# Pressure_gauge_V3_0.net
KiCad netlist of a schematic drawn in Altium Designer
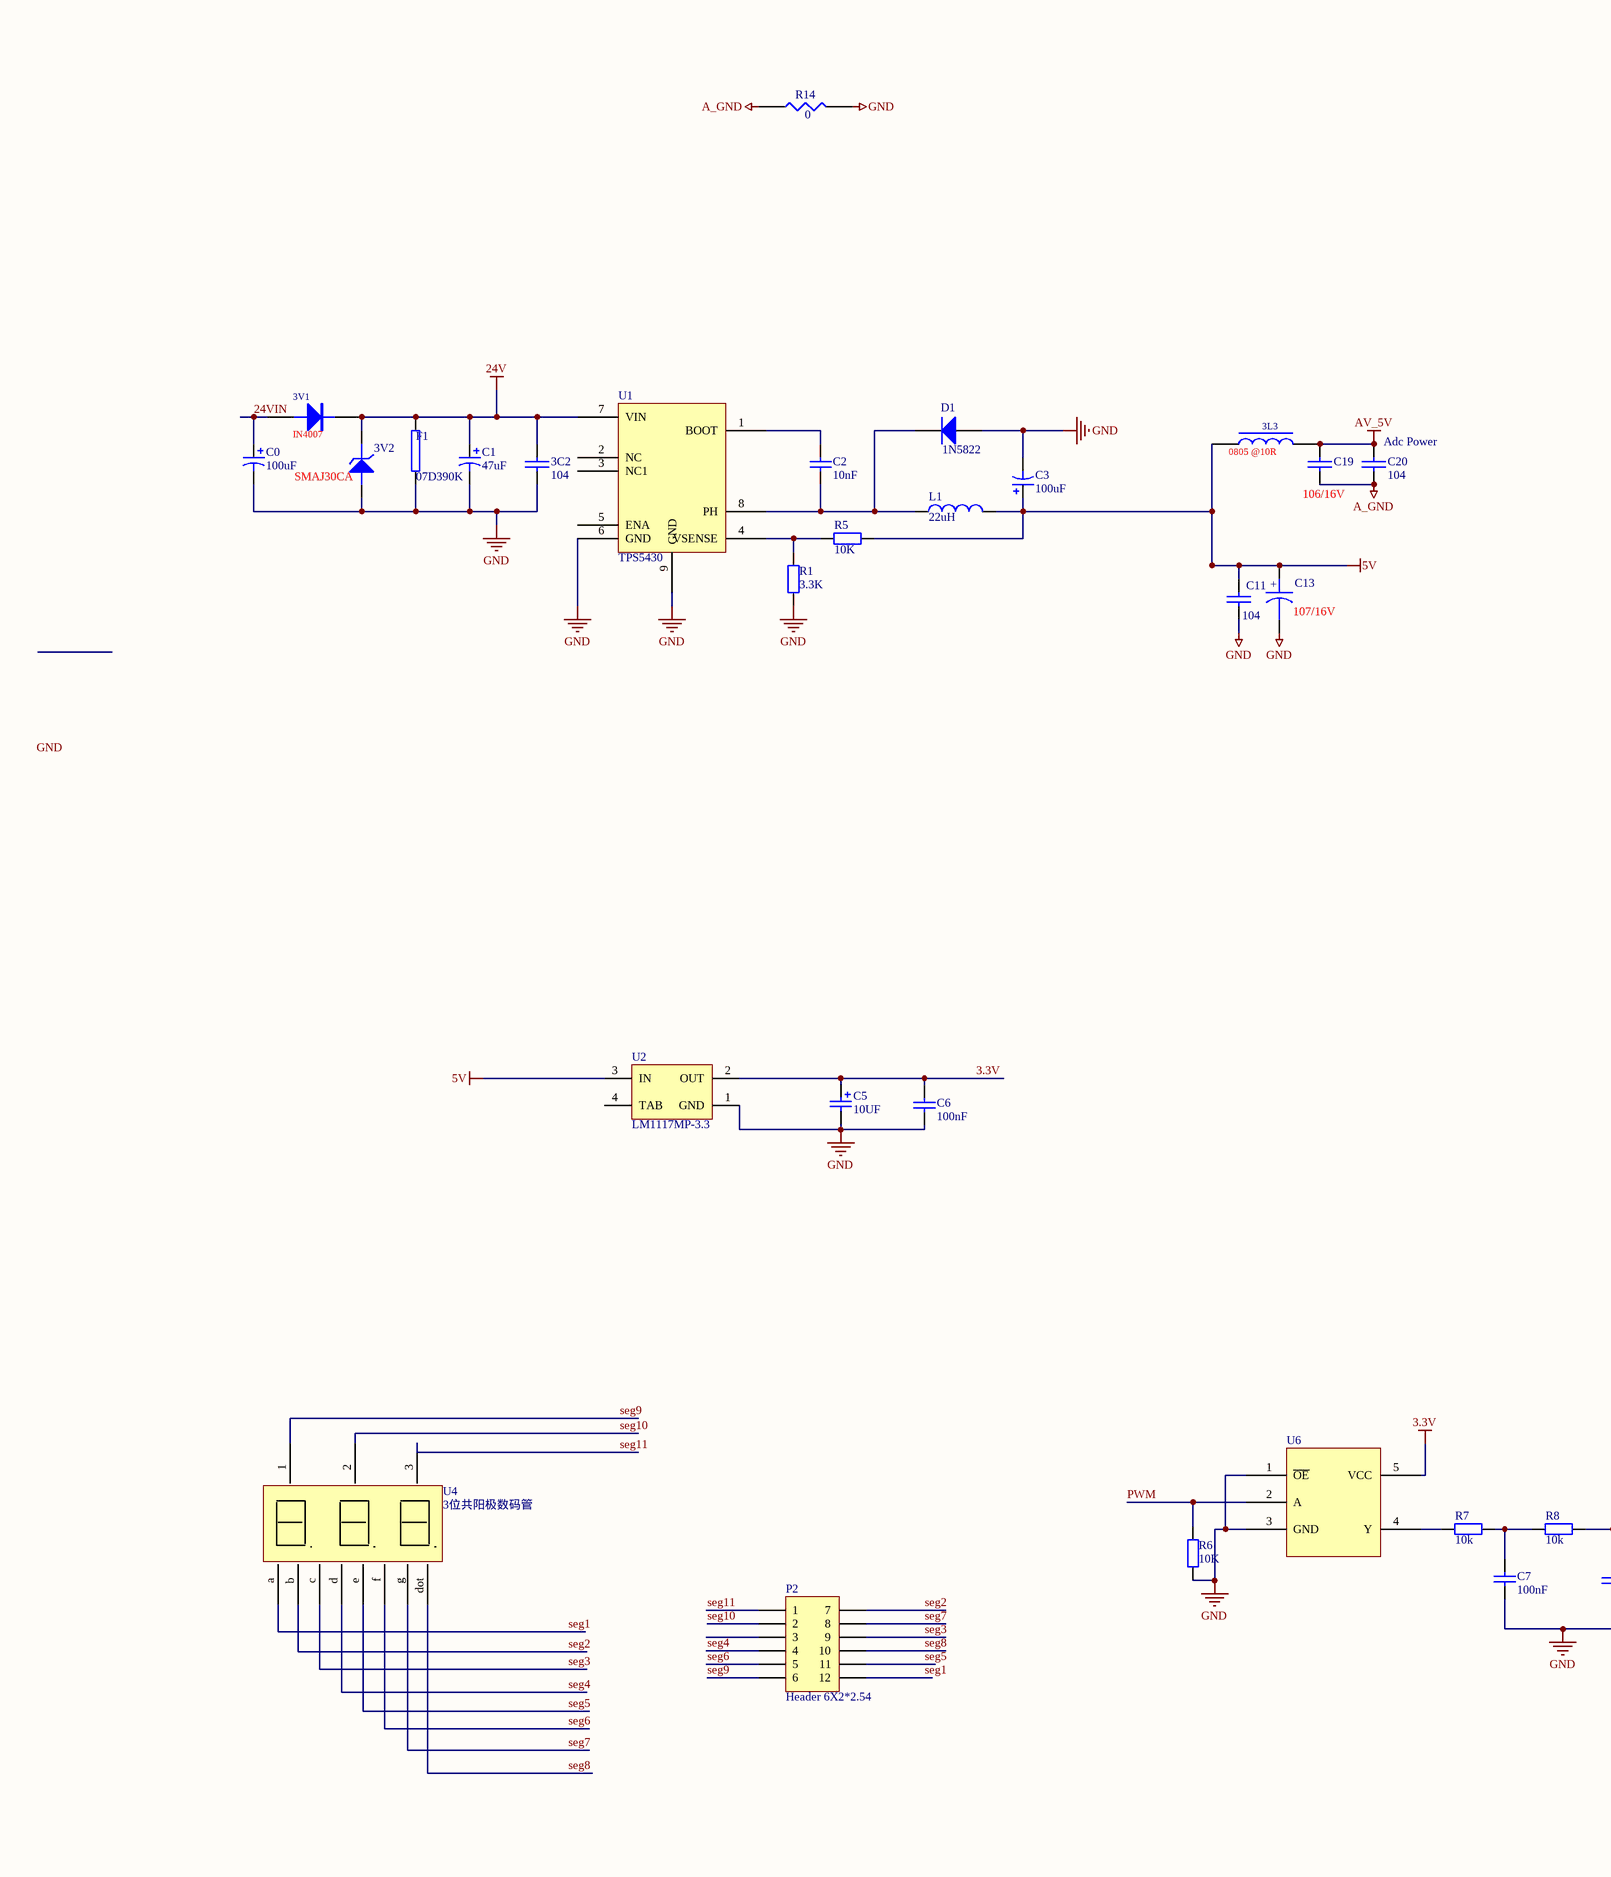
[diagram p0: Pressure_gauge_V3.0.SchDoc, left]
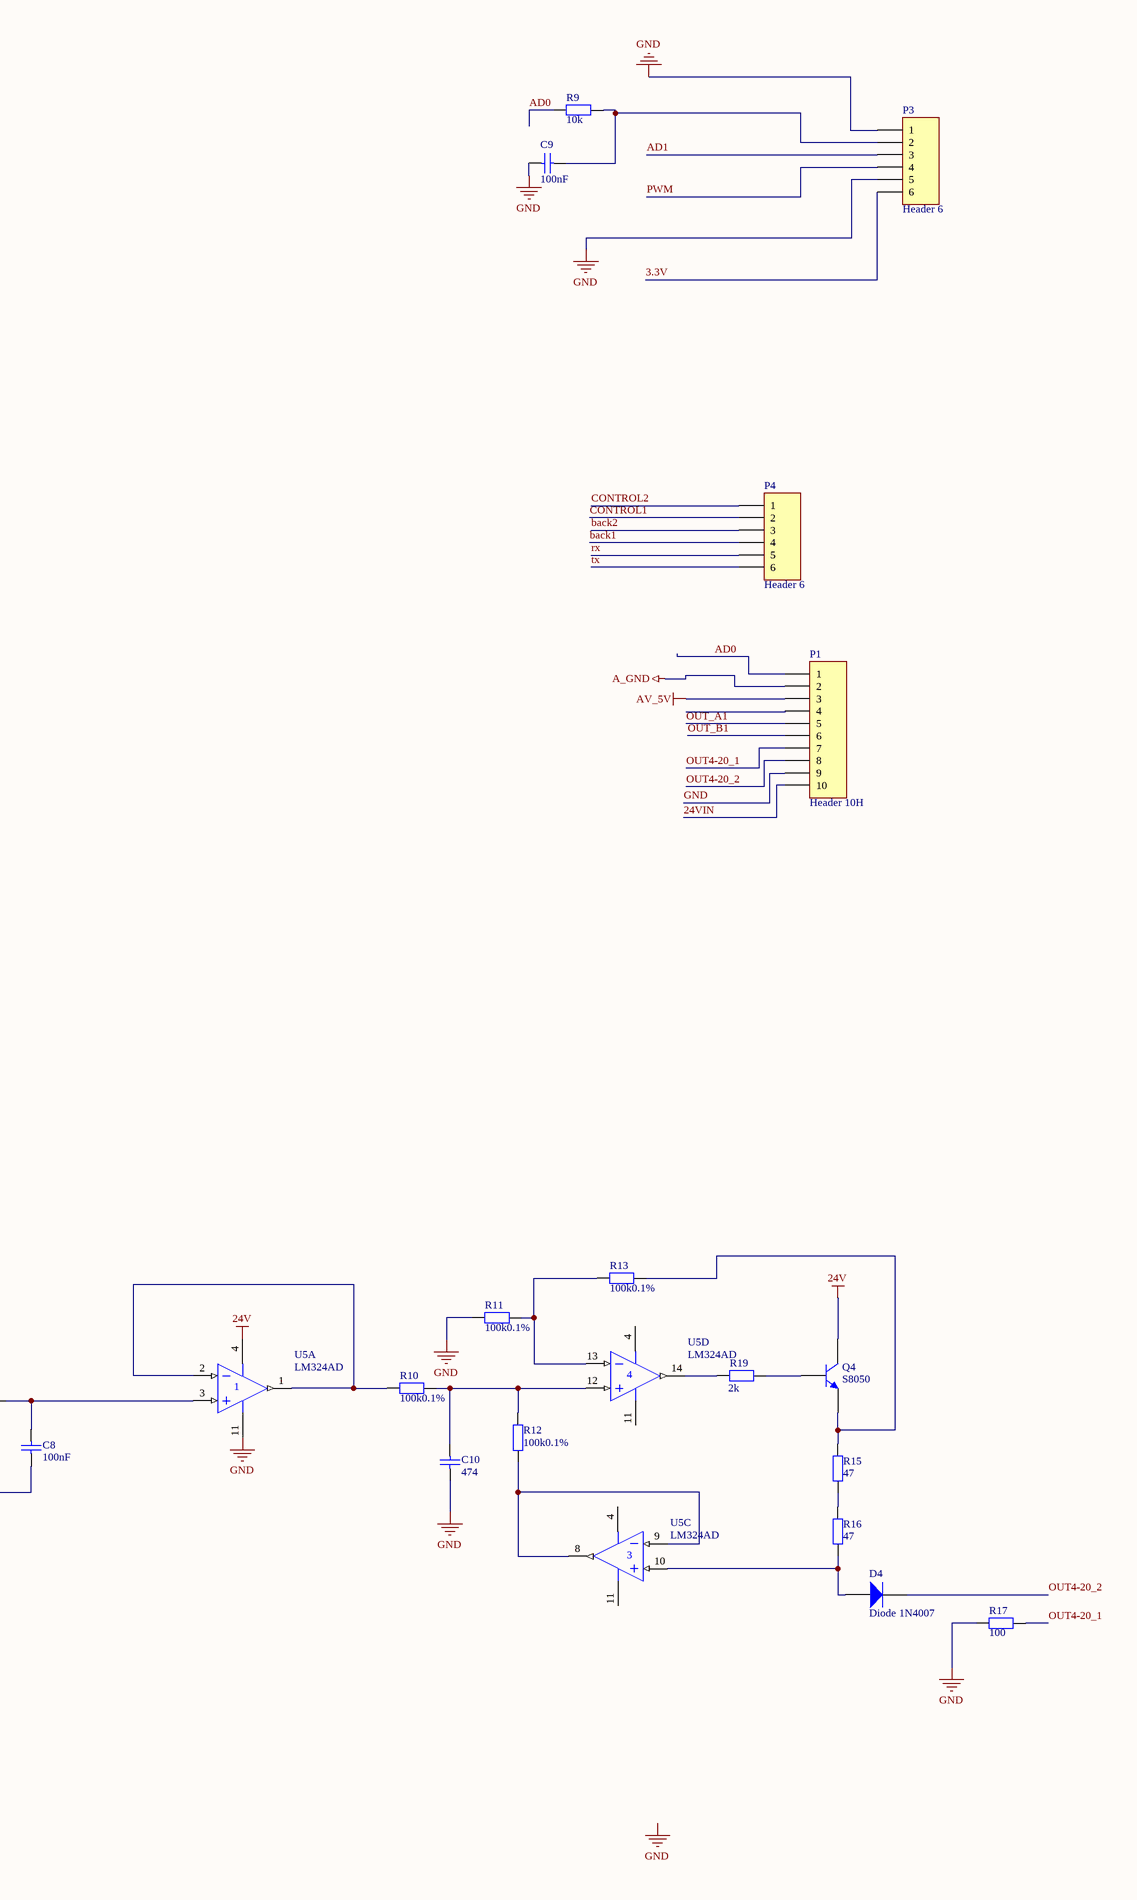
[diagram p1: Pressure_gauge_V3.0.SchDoc, right]

(export (version "E")
  (design (tool "Eeschema 10.0.6"))
  (components
    (comp (ref "3C2")
      (value "104")
      (footprint "0805_C_Y")
      (description "Capacitor")
      (libsource (lib "*") (part "CAP"))
    )
    (comp (ref "3L3")
      (value "0805 @10R")
      (footprint "SMDF4532")
      (description "磁珠")
      (libsource (lib "*") (part "TRANS0"))
    )
    (comp (ref "3V1")
      (value "IN4007")
      (footprint "DO-214AC")
      (description "Diode")
      (libsource (lib "*") (part "DIODE"))
    )
    (comp (ref "3V2")
      (value "SMAJ30CA")
      (footprint "DO-214AA")
      (description "Zener Diode")
      (libsource (lib "*") (part "ZENER3"))
    )
    (comp (ref "C0")
      (value "100uF")
      (footprint "D50")
      (description "Polarized Capacitor (Radial)")
      (fields (field (name "PUBLISHER") "Altium Limited"))
      (libsource (lib "Miscellaneous Devices") (part "Cap Pol1"))
    )
    (comp (ref "C1")
      (value "47uF")
      (footprint "3528 钽电容")
      (description "Polarized Capacitor (Radial)")
      (fields (field (name "PUBLISHER") "Altium Limited"))
      (libsource (lib "Miscellaneous Devices") (part "Cap Pol1"))
    )
    (comp (ref "C2")
      (value "10nF")
      (footprint "0805C")
      (description "Capacitor")
      (fields (field (name "PUBLISHER") "Altium Limited"))
      (libsource (lib "Miscellaneous Devices") (part "Cap"))
    )
    (comp (ref "C3")
      (value "100uF")
      (footprint "1812-PPTC")
      (description "Polarized Capacitor (Radial)")
      (fields (field (name "PUBLISHER") "Altium Limited"))
      (libsource (lib "Miscellaneous Devices") (part "Cap Pol1"))
    )
    (comp (ref "C5")
      (value "10UF")
      (footprint "3216")
      (description "Polarized Capacitor (Axial)")
      (fields (field (name "Comment") "10uf") (field (name "PUBLISHER") "Altium Limited"))
      (libsource (lib "Miscellaneous Devices") (part "Cap Pol2"))
    )
    (comp (ref "C6")
      (value "100nF")
      (footprint "0805_C_Y")
      (description "Capacitor")
      (fields (field (name "Comment") "100nf") (field (name "PUBLISHER") "Altium Limited"))
      (libsource (lib "Miscellaneous Devices") (part "Cap"))
    )
    (comp (ref "C7")
      (value "100nF")
      (footprint "0805_C_Y")
      (description "Capacitor")
      (fields (field (name "Comment") "100nf") (field (name "PUBLISHER") "Altium Limited"))
      (libsource (lib "Miscellaneous Devices") (part "Cap"))
    )
    (comp (ref "C8")
      (value "100nF")
      (footprint "0805_C_Y")
      (description "Capacitor")
      (fields (field (name "Comment") "100nf") (field (name "PUBLISHER") "Altium Limited"))
      (libsource (lib "Miscellaneous Devices") (part "Cap"))
    )
    (comp (ref "C9")
      (value "100nF")
      (footprint "0805_C_Y")
      (description "Capacitor")
      (fields (field (name "Comment") "100nf") (field (name "PUBLISHER") "Altium Limited"))
      (libsource (lib "Miscellaneous Devices") (part "Cap"))
    )
    (comp (ref "C10")
      (value "474")
      (footprint "0805_C_Y")
      (description "Capacitor")
      (fields (field (name "PUBLISHER") "Altium Limited"))
      (libsource (lib "Miscellaneous Devices") (part "Cap"))
    )
    (comp (ref "C11")
      (value "104")
      (footprint "0805_C_Y")
      (description "Capacitor")
      (libsource (lib "*") (part "CAP"))
    )
    (comp (ref "C13")
      (value "107/16V")
      (footprint "3216")
      (description "Capacitor")
      (libsource (lib "*") (part "CAPACITOR POL"))
    )
    (comp (ref "C19")
      (value "106/16V")
      (footprint "XM_ELE_TA_C_6032")
      (description "Capacitor")
      (libsource (lib "*") (part "CAP"))
    )
    (comp (ref "C20")
      (value "104")
      (footprint "0805_C_Y")
      (description "Capacitor")
      (libsource (lib "*") (part "CAP"))
    )
    (comp (ref "D1")
      (value "1N5822")
      (footprint "SMB")
      (description "3 Amp Medium Power Silicon Rectifier Diode")
      (fields (field (name "PUBLISHER") "Altium Limited"))
      (libsource (lib "Miscellaneous Devices") (part "Diode 1N5408"))
    )
    (comp (ref "D4")
      (value "Diode 1N4007")
      (footprint "DO-214")
      (description "3 Amp General Purpose Rectifier")
      (fields (field (name "PUBLISHER") "Altium Limited"))
      (libsource (lib "Miscellaneous Devices") (part "Diode 1N5402"))
    )
    (comp (ref "F1")
      (value "07D390K")
      (footprint "FUSE-220")
      (description "RES")
      (libsource (lib "FTSch") (part "RES2_S"))
    )
    (comp (ref "L1")
      (value "22uH")
      (footprint "SMDRH74")
      (description "Inductor CD74")
      (fields (field (name "PUBLISHER") "Altium Limited"))
      (libsource (lib "Miscellaneous Devices") (part "Inductor"))
    )
    (comp (ref "P1")
      (value "Header 10H")
      (footprint "HDR1X10H")
      (description "Header, 10-Pin, Right Angle")
      (fields (field (name "PUBLISHER") "Altium Limited"))
      (libsource (lib "Miscellaneous Connectors") (part "Header 10H"))
    )
    (comp (ref "P2")
      (value "Header 6X2*2.54")
      (footprint "HDR2X6_CEN")
      (description "Header, 6-Pin, Dual row")
      (fields (field (name "PUBLISHER") "Altium Limited"))
      (libsource (lib "Miscellaneous Connectors") (part "Header 6X2A"))
    )
    (comp (ref "P3")
      (value "Header 6")
      (footprint "HDR1X6")
      (description "Header, 6-Pin")
      (fields (field (name "PUBLISHER") "Altium Limited"))
      (libsource (lib "Miscellaneous Connectors") (part "Header 6"))
    )
    (comp (ref "P4")
      (value "Header 6")
      (footprint "HDR1X6")
      (description "Header, 6-Pin")
      (fields (field (name "PUBLISHER") "Altium Limited"))
      (libsource (lib "Miscellaneous Connectors") (part "Header 6"))
    )
    (comp (ref "Q4")
      (value "S8050")
      (footprint "SOT-23_Y")
      (description "NPN General Purpose Amplifier")
      (fields (field (name "PUBLISHER") "Altium Limited"))
      (libsource (lib "Miscellaneous Devices") (part "2N3904"))
    )
    (comp (ref "R1")
      (value "3.3K")
      (footprint "0805R")
      (description "Resistor")
      (fields (field (name "PUBLISHER") "Altium Limited"))
      (libsource (lib "") (part "Res2_3"))
    )
    (comp (ref "R5")
      (value "10K")
      (footprint "0805R")
      (description "Resistor")
      (fields (field (name "PUBLISHER") "Altium Limited"))
      (libsource (lib "") (part "Res2_2"))
    )
    (comp (ref "R6")
      (value "10K")
      (footprint "0805_R_Y")
      (description "Resistor")
      (fields (field (name "Comment") "10k") (field (name "PUBLISHER") "Altium Limited"))
      (libsource (lib "") (part "Res2_1"))
    )
    (comp (ref "R7")
      (value "10k")
      (footprint "0805_R_Y")
      (description "Resistor")
      (fields (field (name "PUBLISHER") "Altium Limited"))
      (libsource (lib "Miscellaneous Devices") (part "Res2"))
    )
    (comp (ref "R8")
      (value "10k")
      (footprint "0805_R_Y")
      (description "Resistor")
      (fields (field (name "PUBLISHER") "Altium Limited"))
      (libsource (lib "Miscellaneous Devices") (part "Res2"))
    )
    (comp (ref "R9")
      (value "10k")
      (footprint "0805_R_Y")
      (description "Resistor")
      (fields (field (name "PUBLISHER") "Altium Limited"))
      (libsource (lib "Miscellaneous Devices") (part "Res2"))
    )
    (comp (ref "R10")
      (value "100k0.1%")
      (footprint "0805_R_Y")
      (description "Resistor")
      (fields (field (name "PUBLISHER") "Altium Limited"))
      (libsource (lib "Miscellaneous Devices") (part "Res2"))
    )
    (comp (ref "R11")
      (value "100k0.1%")
      (footprint "0805_R_Y")
      (description "Resistor")
      (fields (field (name "PUBLISHER") "Altium Limited"))
      (libsource (lib "Miscellaneous Devices") (part "Res2"))
    )
    (comp (ref "R12")
      (value "100k0.1%")
      (footprint "0805_R_Y")
      (description "Resistor")
      (fields (field (name "PUBLISHER") "Altium Limited"))
      (libsource (lib "") (part "Res2_4"))
    )
    (comp (ref "R13")
      (value "100k0.1%")
      (footprint "0805_R_Y")
      (description "Resistor")
      (fields (field (name "PUBLISHER") "Altium Limited"))
      (libsource (lib "Miscellaneous Devices") (part "Res2"))
    )
    (comp (ref "R14") (value "0") (footprint "0805_R_Y") (libsource (lib "*") (part "RES1")))
    (comp (ref "R15")
      (value "47")
      (footprint "0805_R_Y")
      (description "Resistor")
      (fields (field (name "PUBLISHER") "Altium Limited"))
      (libsource (lib "") (part "Res2_1"))
    )
    (comp (ref "R16")
      (value "47")
      (footprint "0805_R_Y")
      (description "Resistor")
      (fields (field (name "PUBLISHER") "Altium Limited"))
      (libsource (lib "") (part "Res2_1"))
    )
    (comp (ref "R17")
      (value "100")
      (footprint "0805_R_Y")
      (description "Resistor")
      (fields (field (name "PUBLISHER") "Altium Limited"))
      (libsource (lib "Miscellaneous Devices") (part "Res2"))
    )
    (comp (ref "R19")
      (value "2k")
      (footprint "0805_R_Y")
      (description "Resistor")
      (fields (field (name "PUBLISHER") "Altium Limited"))
      (libsource (lib "Miscellaneous Devices") (part "Res2"))
    )
    (comp (ref "U1") (value "TPS5430") (footprint "SO8NB") (libsource (lib "SELFTYPE") (part "Component_1")))
    (comp (ref "U2")
      (value "LM1117MP-3.3")
      (footprint "MP04A_M")
      (description "800mA Low-Dropout Linear Regulator")
      (fields
        (field (name "MANUFACTURER") "National Semiconductor")
        (field (name "DIGIKEYPARTNUMBER") "LM1117MP-3.3CT-ND")
        (field (name "PUBLISHER") "Altium Limited")
      )
      (libsource (lib "NSC LDO") (part "LM1117MP-3.3"))
    )
    (comp (ref "U4") (value "3位共阳极数码管") (footprint "3位数码管0.56") (libsource (lib "kelei") (part "3位共阳极数码管")))
    (comp (ref "U5")
      (value "LM324AD")
      (footprint "D014_N")
      (description "Quadruple Operational Amplifier")
      (fields (field (name "PUBLISHER") "Altium Limited"))
      (libsource (lib "TI Operational Amplifier") (part "LM324AD"))
    )
    (comp (ref "U6")
      (value "NC7SZ125")
      (footprint "SOT23-5")
      (libsource (lib "SEG_pressure gauge_don  V2.1") (part "NC7SZ125"))
    )
  )
  (nets
    (net (code "1") (name "/24VIN") (class "Default")
      (node (ref "3V1") (pin "1") (pinfunction "1_1") (pintype "passive"))
      (node (ref "C0") (pin "1") (pinfunction "1_1") (pintype "passive"))
      (node (ref "P1") (pin "10") (pinfunction "10_10") (pintype "passive"))
    )
    (net (code "2") (name "/AD0") (class "Default")
      (node (ref "P1") (pin "1") (pinfunction "1_1") (pintype "passive"))
      (node (ref "R9") (pin "2") (pinfunction "2_2") (pintype "passive"))
    )
    (net (code "3") (name "/AD1") (class "Default")
      (node (ref "P3") (pin "3") (pinfunction "3_3") (pintype "passive"))
    )
    (net (code "4") (name "/CONTROL1") (class "Default")
      (node (ref "P4") (pin "2") (pinfunction "2_2") (pintype "passive"))
    )
    (net (code "5") (name "/CONTROL2") (class "Default")
      (node (ref "P4") (pin "1") (pinfunction "1_1") (pintype "passive"))
    )
    (net (code "6") (name "/OUT4-20_1") (class "Default")
      (node (ref "P1") (pin "7") (pinfunction "7_7") (pintype "passive"))
      (node (ref "R17") (pin "1") (pinfunction "1_1") (pintype "passive"))
    )
    (net (code "7") (name "/OUT4-20_2") (class "Default")
      (node (ref "D4") (pin "2") (pinfunction "K_2") (pintype "passive"))
      (node (ref "P1") (pin "8") (pinfunction "8_8") (pintype "passive"))
    )
    (net (code "8") (name "/OUT_A1") (class "Default")
      (node (ref "P1") (pin "5") (pinfunction "5_5") (pintype "passive"))
    )
    (net (code "9") (name "/OUT_B1") (class "Default")
      (node (ref "P1") (pin "6") (pinfunction "6_6") (pintype "passive"))
    )
    (net (code "10") (name "/PWM") (class "Default")
      (node (ref "P3") (pin "4") (pinfunction "4_4") (pintype "passive"))
      (node (ref "R6") (pin "1") (pinfunction "1_1") (pintype "passive"))
      (node (ref "U6") (pin "2") (pinfunction "A_2") (pintype "passive"))
    )
    (net (code "11") (name "/back1") (class "Default")
      (node (ref "P4") (pin "4") (pinfunction "4_4") (pintype "passive"))
    )
    (net (code "12") (name "/back2") (class "Default")
      (node (ref "P4") (pin "3") (pinfunction "3_3") (pintype "passive"))
    )
    (net (code "13") (name "/rx") (class "Default")
      (node (ref "P4") (pin "5") (pinfunction "5_5") (pintype "passive"))
    )
    (net (code "14") (name "/seg1") (class "Default")
      (node (ref "P2") (pin "12") (pinfunction "12_12") (pintype "passive"))
      (node (ref "U4") (pin "a") (pinfunction "a_a") (pintype "passive"))
    )
    (net (code "15") (name "/seg2") (class "Default")
      (node (ref "P2") (pin "7") (pinfunction "7_7") (pintype "passive"))
      (node (ref "U4") (pin "b") (pinfunction "b_b") (pintype "passive"))
    )
    (net (code "16") (name "/seg3") (class "Default")
      (node (ref "P2") (pin "9") (pinfunction "9_9") (pintype "passive"))
      (node (ref "U4") (pin "c") (pinfunction "c_c") (pintype "passive"))
    )
    (net (code "17") (name "/seg4") (class "Default")
      (node (ref "P2") (pin "4") (pinfunction "4_4") (pintype "passive"))
      (node (ref "U4") (pin "d") (pinfunction "d_d") (pintype "passive"))
    )
    (net (code "18") (name "/seg5") (class "Default")
      (node (ref "P2") (pin "11") (pinfunction "11_11") (pintype "passive"))
      (node (ref "U4") (pin "e") (pinfunction "e_e") (pintype "passive"))
    )
    (net (code "19") (name "/seg6") (class "Default")
      (node (ref "P2") (pin "5") (pinfunction "5_5") (pintype "passive"))
      (node (ref "U4") (pin "f") (pinfunction "f_f") (pintype "passive"))
    )
    (net (code "20") (name "/seg7") (class "Default")
      (node (ref "P2") (pin "8") (pinfunction "8_8") (pintype "passive"))
      (node (ref "U4") (pin "g") (pinfunction "g_g") (pintype "passive"))
    )
    (net (code "21") (name "/seg8") (class "Default")
      (node (ref "P2") (pin "10") (pinfunction "10_10") (pintype "passive"))
      (node (ref "U4") (pin "dot") (pinfunction "dot_dot") (pintype "passive"))
    )
    (net (code "22") (name "/seg9") (class "Default")
      (node (ref "P2") (pin "6") (pinfunction "6_6") (pintype "passive"))
      (node (ref "U4") (pin "1") (pinfunction "1_1") (pintype "passive"))
    )
    (net (code "23") (name "/seg10") (class "Default")
      (node (ref "P2") (pin "2") (pinfunction "2_2") (pintype "passive"))
      (node (ref "U4") (pin "2") (pinfunction "2_2") (pintype "passive"))
    )
    (net (code "24") (name "/seg11") (class "Default")
      (node (ref "P2") (pin "1") (pinfunction "1_1") (pintype "passive"))
      (node (ref "U4") (pin "3") (pinfunction "3_3") (pintype "passive"))
    )
    (net (code "25") (name "/tx") (class "Default")
      (node (ref "P4") (pin "6") (pinfunction "6_6") (pintype "passive"))
    )
    (net (code "26") (name "3.3V") (class "Default")
      (node (ref "C5") (pin "1") (pinfunction "1_1") (pintype "passive"))
      (node (ref "C6") (pin "1") (pinfunction "1_1") (pintype "passive"))
      (node (ref "P3") (pin "6") (pinfunction "6_6") (pintype "passive"))
      (node (ref "U2") (pin "2") (pinfunction "OUT_2") (pintype "power_in"))
      (node (ref "U6") (pin "5") (pinfunction "VCC_5") (pintype "passive"))
    )
    (net (code "27") (name "5V") (class "Default")
      (node (ref "3L3") (pin "1") (pinfunction "1_1") (pintype "passive"))
      (node (ref "C11") (pin "1") (pinfunction "1_1") (pintype "passive"))
      (node (ref "C13") (pin "1") (pinfunction "1_1") (pintype "passive"))
      (node (ref "C3") (pin "1") (pinfunction "1_1") (pintype "passive"))
      (node (ref "L1") (pin "2") (pinfunction "2_2") (pintype "passive"))
      (node (ref "R5") (pin "2") (pinfunction "2_2") (pintype "passive"))
      (node (ref "U2") (pin "3") (pinfunction "IN_3") (pintype "power_in"))
    )
    (net (code "28") (name "24V") (class "Default")
      (node (ref "3C2") (pin "1") (pinfunction "1_1") (pintype "passive"))
      (node (ref "3V1") (pin "2") (pinfunction "2_2") (pintype "passive"))
      (node (ref "3V2") (pin "2") (pinfunction "K_2") (pintype "passive"))
      (node (ref "C1") (pin "1") (pinfunction "1_1") (pintype "passive"))
      (node (ref "F1") (pin "1") (pinfunction "1_1") (pintype "passive"))
      (node (ref "Q4") (pin "3") (pinfunction "C_3") (pintype "passive"))
      (node (ref "U1") (pin "7") (pinfunction "VIN_7") (pintype "passive"))
      (node (ref "U5") (pin "4") (pinfunction "V+_4") (pintype "power_in"))
    )
    (net (code "29") (name "AV_5V") (class "Default")
      (node (ref "3L3") (pin "2") (pinfunction "2_2") (pintype "passive"))
      (node (ref "C19") (pin "1") (pinfunction "1_1") (pintype "passive"))
      (node (ref "C20") (pin "1") (pinfunction "1_1") (pintype "passive"))
      (node (ref "P1") (pin "3") (pinfunction "3_3") (pintype "passive"))
    )
    (net (code "30") (name "A_GND") (class "Default")
      (node (ref "C19") (pin "2") (pinfunction "2_2") (pintype "passive"))
      (node (ref "C20") (pin "2") (pinfunction "2_2") (pintype "passive"))
      (node (ref "P1") (pin "2") (pinfunction "2_2") (pintype "passive"))
      (node (ref "R14") (pin "1") (pinfunction "1_1") (pintype "passive"))
    )
    (net (code "31") (name "GND") (class "Default")
      (node (ref "3C2") (pin "2") (pinfunction "2_2") (pintype "passive"))
      (node (ref "3V2") (pin "1") (pinfunction "A_1") (pintype "passive"))
      (node (ref "C0") (pin "2") (pinfunction "2_2") (pintype "passive"))
      (node (ref "C1") (pin "2") (pinfunction "2_2") (pintype "passive"))
      (node (ref "C10") (pin "2") (pinfunction "2_2") (pintype "passive"))
      (node (ref "C11") (pin "2") (pinfunction "2_2") (pintype "passive"))
      (node (ref "C13") (pin "2") (pinfunction "2_2") (pintype "passive"))
      (node (ref "C3") (pin "2") (pinfunction "2_2") (pintype "passive"))
      (node (ref "C5") (pin "2") (pinfunction "2_2") (pintype "passive"))
      (node (ref "C6") (pin "2") (pinfunction "2_2") (pintype "passive"))
      (node (ref "C7") (pin "2") (pinfunction "2_2") (pintype "passive"))
      (node (ref "C8") (pin "2") (pinfunction "2_2") (pintype "passive"))
      (node (ref "C9") (pin "1") (pinfunction "1_1") (pintype "passive"))
      (node (ref "D1") (pin "1") (pinfunction "A_1") (pintype "passive"))
      (node (ref "F1") (pin "2") (pinfunction "2_2") (pintype "passive"))
      (node (ref "P1") (pin "9") (pinfunction "9_9") (pintype "passive"))
      (node (ref "P3") (pin "1") (pinfunction "1_1") (pintype "passive"))
      (node (ref "P3") (pin "5") (pinfunction "5_5") (pintype "passive"))
      (node (ref "R1") (pin "1") (pinfunction "1_1") (pintype "passive"))
      (node (ref "R11") (pin "2") (pinfunction "2_2") (pintype "passive"))
      (node (ref "R14") (pin "2") (pinfunction "2_2") (pintype "passive"))
      (node (ref "R17") (pin "2") (pinfunction "2_2") (pintype "passive"))
      (node (ref "R6") (pin "2") (pinfunction "2_2") (pintype "passive"))
      (node (ref "U1") (pin "6") (pinfunction "GND_6") (pintype "passive"))
      (node (ref "U1") (pin "9") (pinfunction "GND_9") (pintype "passive"))
      (node (ref "U2") (pin "1") (pinfunction "GND_1") (pintype "power_in"))
      (node (ref "U5") (pin "11") (pinfunction "V-_11") (pintype "power_in"))
      (node (ref "U6") (pin "1") (pinfunction "~{OE}_1") (pintype "passive"))
      (node (ref "U6") (pin "3") (pinfunction "GND_3") (pintype "passive"))
    )
    (net (code "32") (name "Net-(C7-Pad1)") (class "Default")
      (node (ref "C7") (pin "1") (pinfunction "1_1") (pintype "passive"))
      (node (ref "R7") (pin "1") (pinfunction "1_1") (pintype "passive"))
      (node (ref "R8") (pin "2") (pinfunction "2_2") (pintype "passive"))
    )
    (net (code "33") (name "Net-(C9-Pad2)") (class "Default")
      (node (ref "C9") (pin "2") (pinfunction "2_2") (pintype "passive"))
      (node (ref "P3") (pin "2") (pinfunction "2_2") (pintype "passive"))
      (node (ref "R9") (pin "1") (pinfunction "1_1") (pintype "passive"))
    )
    (net (code "34") (name "Net-(D1-K)") (class "Default")
      (node (ref "C2") (pin "1") (pinfunction "1_1") (pintype "passive"))
      (node (ref "D1") (pin "2") (pinfunction "K_2") (pintype "passive"))
      (node (ref "L1") (pin "1") (pinfunction "1_1") (pintype "passive"))
      (node (ref "U1") (pin "8") (pinfunction "PH_8") (pintype "passive"))
    )
    (net (code "35") (name "Net-(D4-A)") (class "Default")
      (node (ref "D4") (pin "1") (pinfunction "A_1") (pintype "passive"))
      (node (ref "R16") (pin "2") (pinfunction "2_2") (pintype "passive"))
      (node (ref "U5") (pin "10") (pinfunction "IN+_10") (pintype "input"))
    )
    (net (code "36") (name "Net-(Q4-B)") (class "Default")
      (node (ref "Q4") (pin "1") (pinfunction "B_1") (pintype "passive"))
      (node (ref "R19") (pin "1") (pinfunction "1_1") (pintype "passive"))
    )
    (net (code "37") (name "Net-(Q4-E)") (class "Default")
      (node (ref "Q4") (pin "2") (pinfunction "E_2") (pintype "passive"))
      (node (ref "R13") (pin "1") (pinfunction "1_1") (pintype "passive"))
      (node (ref "R15") (pin "1") (pinfunction "1_1") (pintype "passive"))
    )
    (net (code "38") (name "Net-(R15-Pad2)") (class "Default")
      (node (ref "R15") (pin "2") (pinfunction "2_2") (pintype "passive"))
      (node (ref "R16") (pin "1") (pinfunction "1_1") (pintype "passive"))
    )
    (net (code "39") (name "Net-(U1-BOOT)") (class "Default")
      (node (ref "C2") (pin "2") (pinfunction "2_2") (pintype "passive"))
      (node (ref "U1") (pin "1") (pinfunction "BOOT_1") (pintype "passive"))
    )
    (net (code "40") (name "Net-(U1-VSENSE)") (class "Default")
      (node (ref "R1") (pin "2") (pinfunction "2_2") (pintype "passive"))
      (node (ref "R5") (pin "1") (pinfunction "1_1") (pintype "passive"))
      (node (ref "U1") (pin "4") (pinfunction "VSENSE_4") (pintype "passive"))
    )
    (net (code "41") (name "Net-(U5A-IN+)") (class "Default")
      (node (ref "C8") (pin "1") (pinfunction "1_1") (pintype "passive"))
      (node (ref "R8") (pin "1") (pinfunction "1_1") (pintype "passive"))
      (node (ref "U5") (pin "3") (pinfunction "IN+_3") (pintype "input"))
    )
    (net (code "42") (name "Net-(U5A-IN-)") (class "Default")
      (node (ref "R10") (pin "2") (pinfunction "2_2") (pintype "passive"))
      (node (ref "U5") (pin "1") (pinfunction "OUT_1") (pintype "output"))
      (node (ref "U5") (pin "2") (pinfunction "IN-_2") (pintype "input"))
    )
    (net (code "43") (name "Net-(U5C-IN-)") (class "Default")
      (node (ref "R12") (pin "1") (pinfunction "1_1") (pintype "passive"))
      (node (ref "U5") (pin "8") (pinfunction "OUT_8") (pintype "output"))
      (node (ref "U5") (pin "9") (pinfunction "IN-_9") (pintype "input"))
    )
    (net (code "44") (name "Net-(U5D-IN+)") (class "Default")
      (node (ref "C10") (pin "1") (pinfunction "1_1") (pintype "passive"))
      (node (ref "R10") (pin "1") (pinfunction "1_1") (pintype "passive"))
      (node (ref "R12") (pin "2") (pinfunction "2_2") (pintype "passive"))
      (node (ref "U5") (pin "12") (pinfunction "IN+_12") (pintype "input"))
    )
    (net (code "45") (name "Net-(U5D-IN-)") (class "Default")
      (node (ref "R11") (pin "1") (pinfunction "1_1") (pintype "passive"))
      (node (ref "R13") (pin "2") (pinfunction "2_2") (pintype "passive"))
      (node (ref "U5") (pin "13") (pinfunction "IN-_13") (pintype "input"))
    )
    (net (code "46") (name "Net-(U5D-OUT)") (class "Default")
      (node (ref "R19") (pin "2") (pinfunction "2_2") (pintype "passive"))
      (node (ref "U5") (pin "14") (pinfunction "OUT_14") (pintype "output"))
    )
    (net (code "47") (name "Net-(U6-Y)") (class "Default")
      (node (ref "R7") (pin "2") (pinfunction "2_2") (pintype "passive"))
      (node (ref "U6") (pin "4") (pinfunction "Y_4") (pintype "passive"))
    )
    (net (code "48") (name "unconnected-(P1-Pad4)") (class "Default")
      (node (ref "P1") (pin "4") (pinfunction "4_4") (pintype "passive"))
    )
    (net (code "49") (name "unconnected-(P2-Pad3)") (class "Default")
      (node (ref "P2") (pin "3") (pinfunction "3_3") (pintype "passive"))
    )
    (net (code "50") (name "unconnected-(U1-ENA-Pad5)") (class "Default")
      (node (ref "U1") (pin "5") (pinfunction "ENA_5") (pintype "passive"))
    )
    (net (code "51") (name "unconnected-(U1-NC-Pad2)") (class "Default")
      (node (ref "U1") (pin "2") (pinfunction "NC_2") (pintype "passive"))
    )
    (net (code "52") (name "unconnected-(U1-NC1-Pad3)") (class "Default")
      (node (ref "U1") (pin "3") (pinfunction "NC1_3") (pintype "passive"))
    )
    (net (code "53") (name "unconnected-(U2-TAB-Pad4)") (class "Default")
      (node (ref "U2") (pin "4") (pinfunction "TAB_4") (pintype "power_in"))
    )
    (net (code "54") (name "unconnected-(U5C-V+-Pad4)") (class "Default")
      (node (ref "U5") (pin "4") (pinfunction "V+_4") (pintype "power_in"))
    )
    (net (code "55") (name "unconnected-(U5C-V--Pad11)") (class "Default")
      (node (ref "U5") (pin "11") (pinfunction "V-_11") (pintype "power_in"))
    )
    (net (code "56") (name "unconnected-(U5D-V+-Pad4)") (class "Default")
      (node (ref "U5") (pin "4") (pinfunction "V+_4") (pintype "power_in"))
    )
    (net (code "57") (name "unconnected-(U5D-V--Pad11)") (class "Default")
      (node (ref "U5") (pin "11") (pinfunction "V-_11") (pintype "power_in"))
    )
  )
)
